# CO2-Ampel_v11.net
KiCad netlist of a schematic drawn in EAGLE
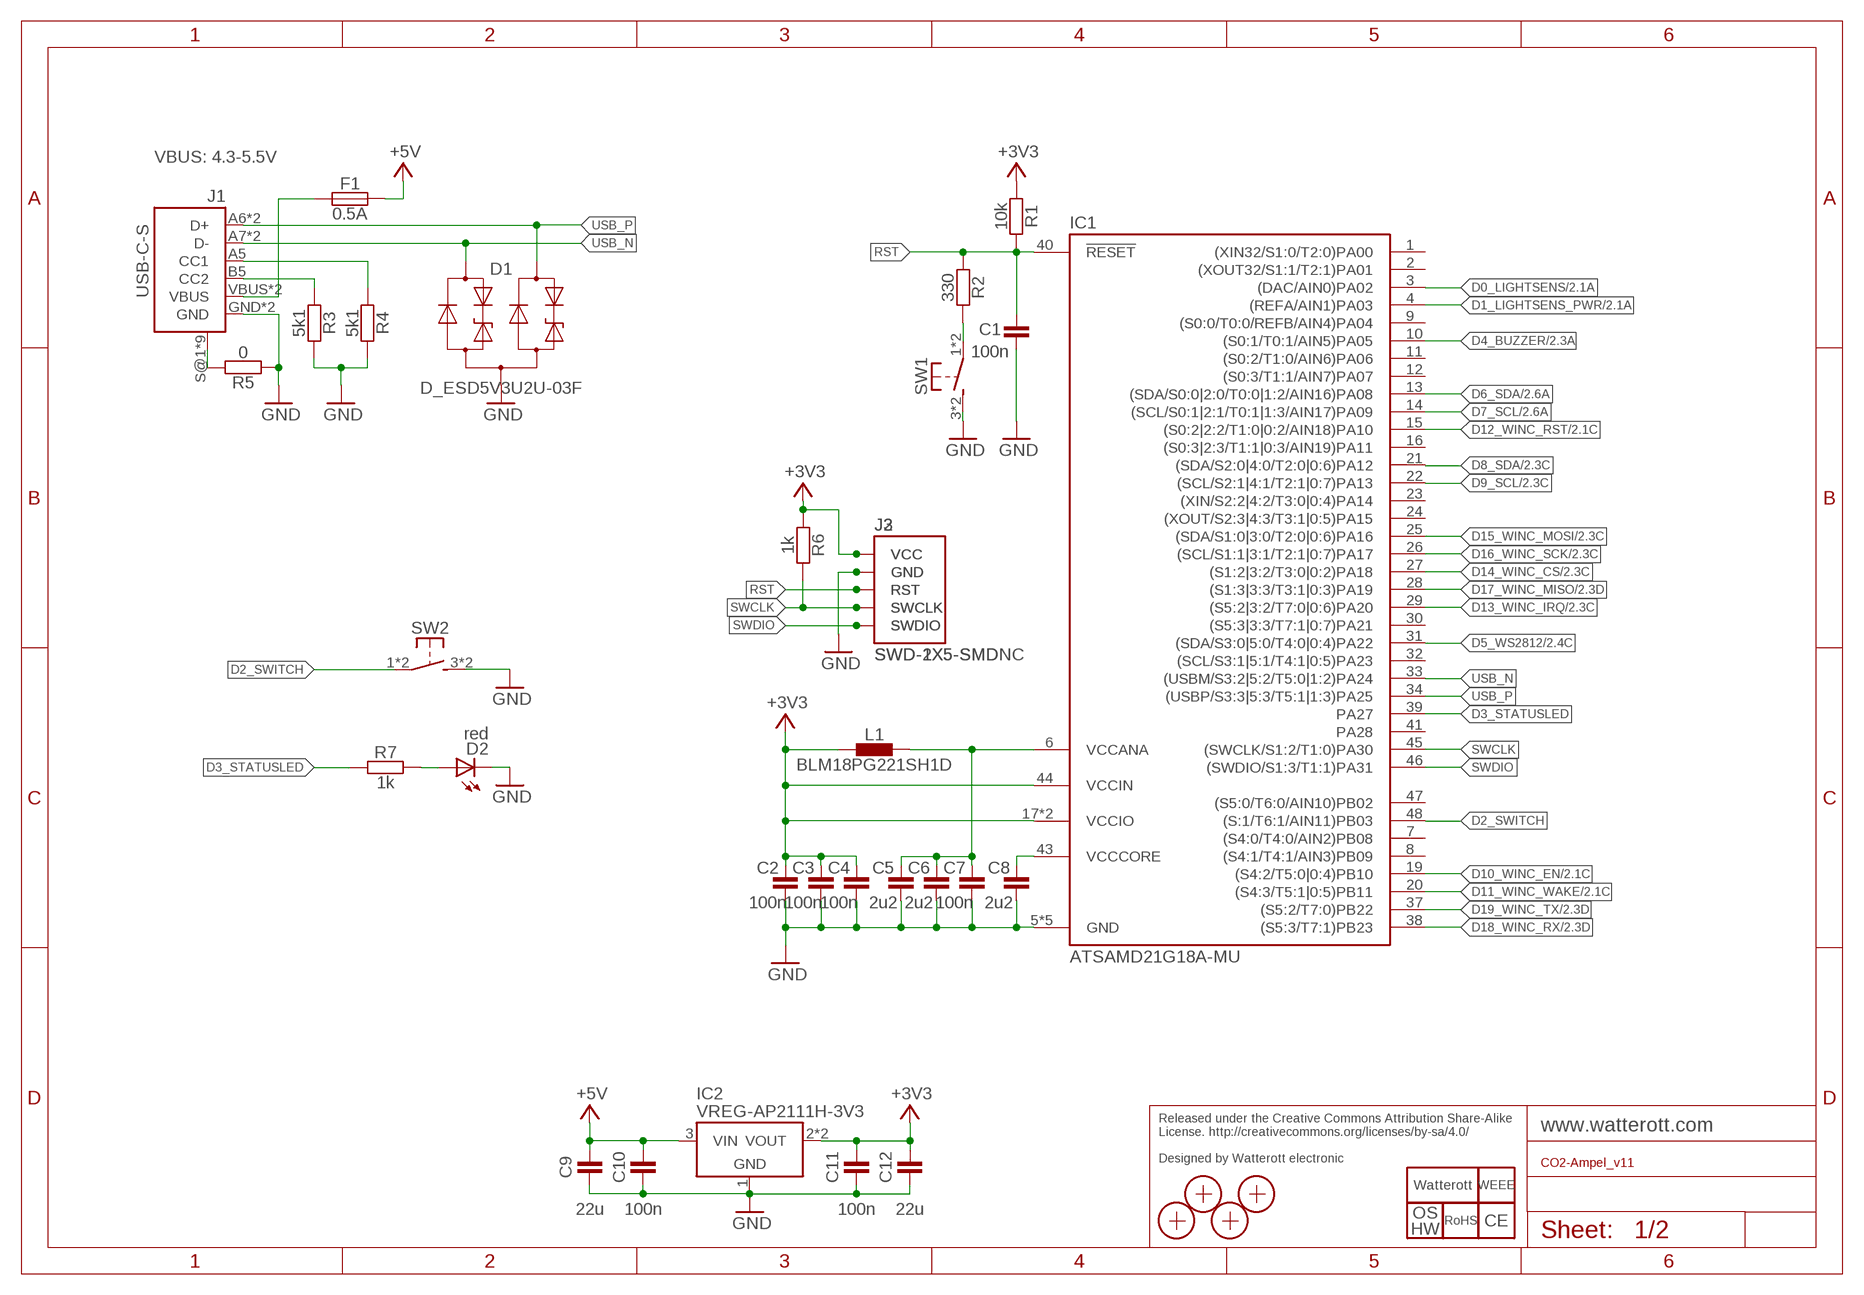
[diagram p0: schematic, sheet 1]
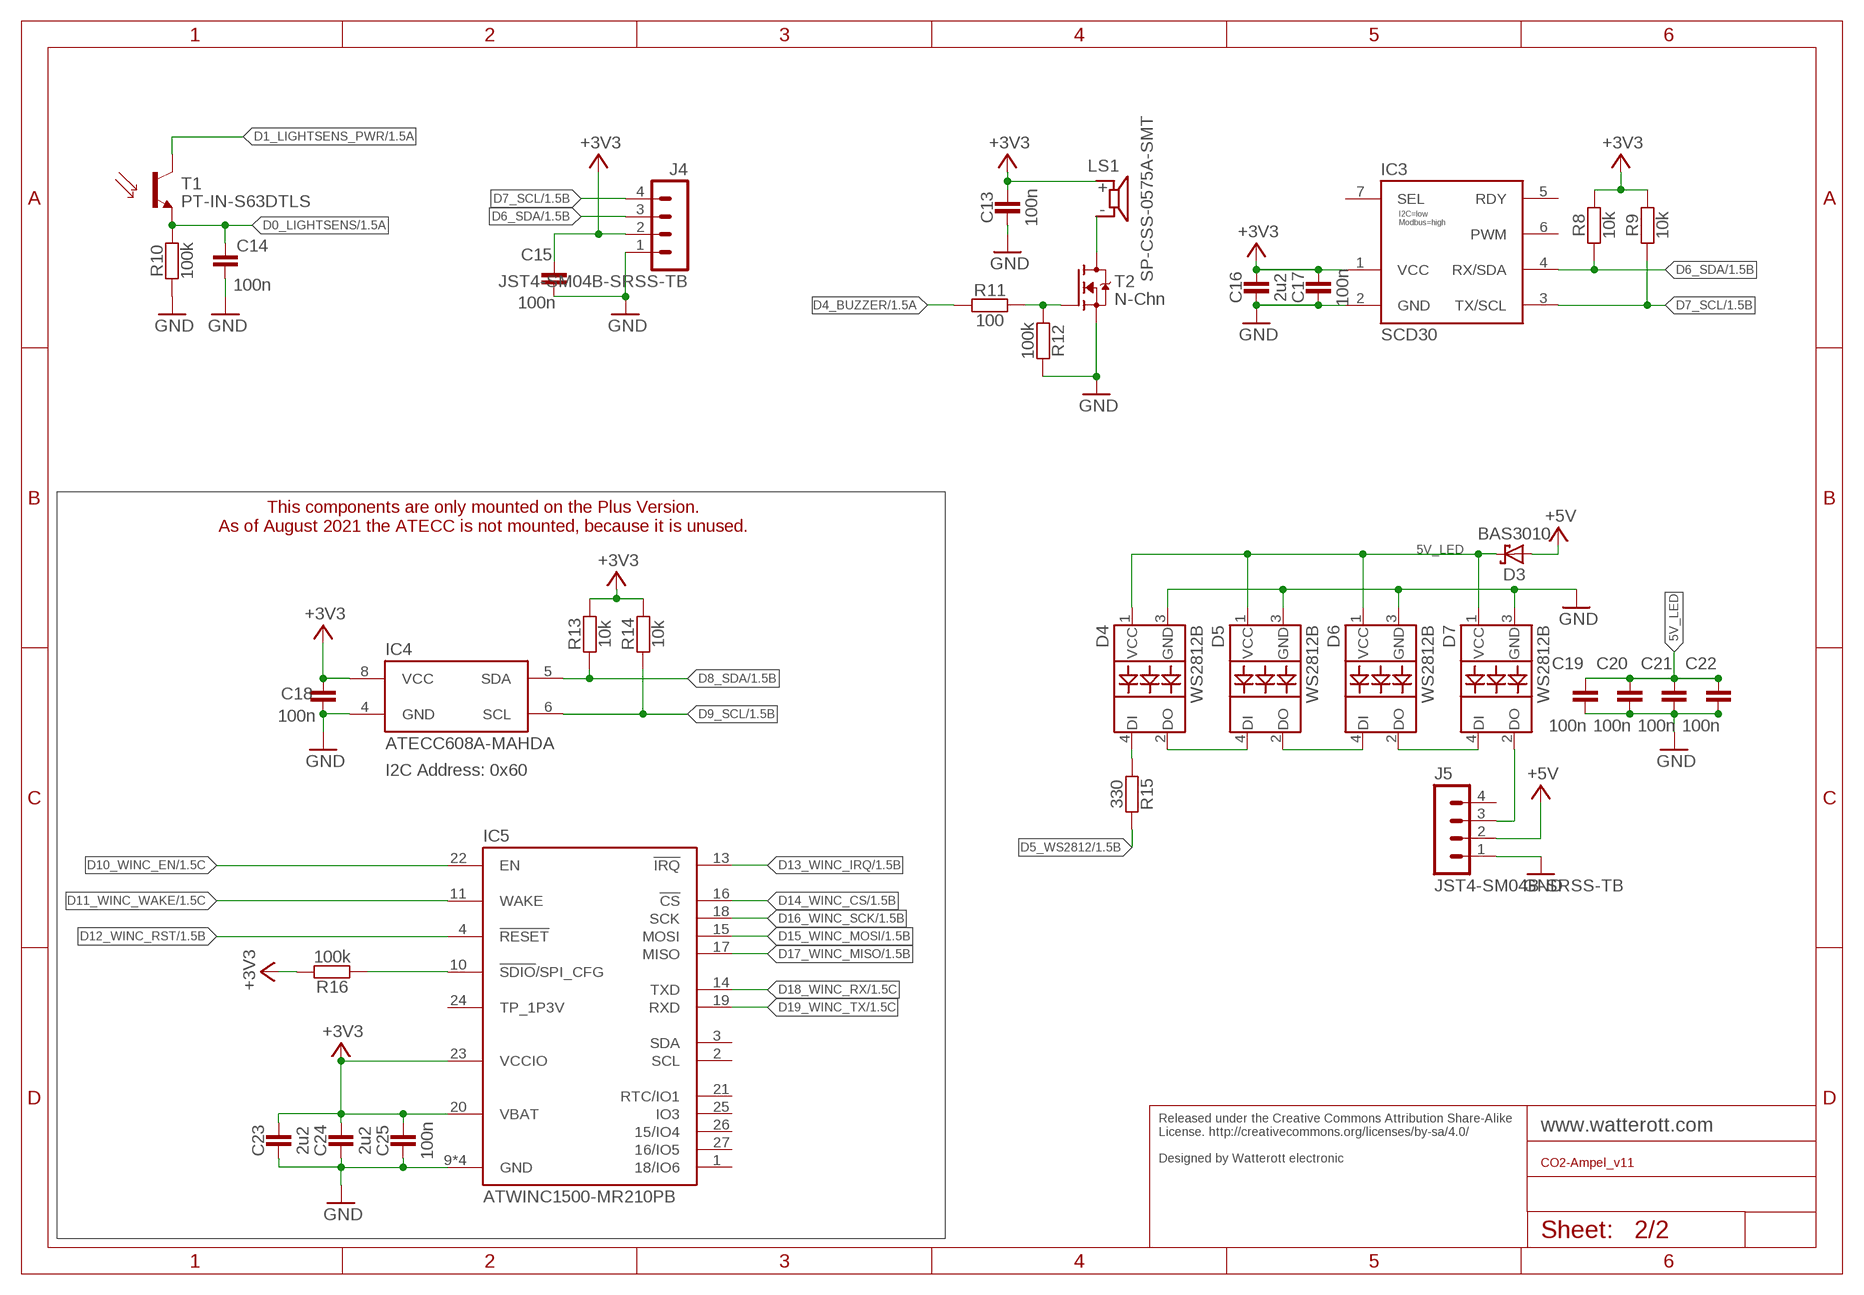
[diagram p1: schematic, sheet 2]

(export (version "E")
  (design (tool "Eeschema 10.0.6"))
  (components
    (comp (ref "C1")
      (value "100n")
      (footprint "eagle-import:C0402")
      (libsource (lib "eagle-import") (part "CAPACITOR-0402"))
    )
    (comp (ref "C2")
      (value "100n")
      (footprint "eagle-import:C0402")
      (libsource (lib "eagle-import") (part "CAPACITOR-0402"))
    )
    (comp (ref "C3")
      (value "100n")
      (footprint "eagle-import:C0402")
      (libsource (lib "eagle-import") (part "CAPACITOR-0402"))
    )
    (comp (ref "C4")
      (value "100n")
      (footprint "eagle-import:C0402")
      (libsource (lib "eagle-import") (part "CAPACITOR-0402"))
    )
    (comp (ref "C5")
      (value "2u2")
      (footprint "eagle-import:C0402")
      (libsource (lib "eagle-import") (part "CAPACITOR-0402"))
    )
    (comp (ref "C6")
      (value "2u2")
      (footprint "eagle-import:C0402")
      (libsource (lib "eagle-import") (part "CAPACITOR-0402"))
    )
    (comp (ref "C7")
      (value "100n")
      (footprint "eagle-import:C0402")
      (libsource (lib "eagle-import") (part "CAPACITOR-0402"))
    )
    (comp (ref "C8")
      (value "2u2")
      (footprint "eagle-import:C0402")
      (libsource (lib "eagle-import") (part "CAPACITOR-0402"))
    )
    (comp (ref "C9")
      (value "22u")
      (footprint "eagle-import:C0805")
      (libsource (lib "eagle-import") (part "CAPACITOR-0805"))
    )
    (comp (ref "C10")
      (value "100n")
      (footprint "eagle-import:C0402")
      (libsource (lib "eagle-import") (part "CAPACITOR-0402"))
    )
    (comp (ref "C11")
      (value "100n")
      (footprint "eagle-import:C0402")
      (libsource (lib "eagle-import") (part "CAPACITOR-0402"))
    )
    (comp (ref "C12")
      (value "22u")
      (footprint "eagle-import:C0805")
      (libsource (lib "eagle-import") (part "CAPACITOR-0805"))
    )
    (comp (ref "D1")
      (value "D_ESD5V3U2U-03F")
      (footprint "eagle-import:SOT723")
      (libsource (lib "eagle-import") (part "D_ESD5V3U2U-03F"))
    )
    (comp (ref "D2")
      (value "red")
      (footprint "eagle-import:C0603")
      (libsource (lib "eagle-import") (part "LED-0603"))
    )
    (comp (ref "F1")
      (value "0.5A")
      (footprint "eagle-import:C0805")
      (libsource (lib "eagle-import") (part "FUSE-0805"))
    )
    (comp (ref "IC1")
      (value "ATSAMD21G18A-MU")
      (footprint "eagle-import:QFN48-PAD")
      (libsource (lib "eagle-import") (part "ATSAMD21G18A-MU"))
    )
    (comp (ref "IC2")
      (value "VREG-AP2111H-3V3")
      (footprint "eagle-import:SOT223")
      (libsource (lib "eagle-import") (part "VREG-TS1117CW-3V3"))
    )
    (comp (ref "J1")
      (value "USB-C-S")
      (footprint "eagle-import:USB-C-S")
      (libsource (lib "eagle-import") (part "USB-C-S"))
    )
    (comp (ref "J2")
      (value "SWD-2X5-SMD")
      (footprint "eagle-import:SWD-2X5_SMD")
      (libsource (lib "eagle-import") (part "SWD-2X5-SMD"))
    )
    (comp (ref "J3")
      (value "SWD-1X5-SMDNC")
      (footprint "eagle-import:SWD-1X5_SMDNC")
      (libsource (lib "eagle-import") (part "SWD-1X5-SMDNC"))
    )
    (comp (ref "L1")
      (value "BLM18PG221SH1D")
      (footprint "eagle-import:C0603")
      (libsource (lib "eagle-import") (part "INDUCTOR-0603"))
    )
    (comp (ref "LOGO1")
      (value "LOGO_SPARK-4")
      (footprint "eagle-import:SPARK_4MM")
      (libsource (lib "eagle-import") (part "LOGO_SPARK-4"))
    )
    (comp (ref "LOGO2")
      (value "LOGO_WEEE-4")
      (footprint "eagle-import:WEEE_4MM")
      (libsource (lib "eagle-import") (part "LOGO_WEEE-4"))
    )
    (comp (ref "LOGO3")
      (value "OSHW_LOGOX0070")
      (footprint "eagle-import:OSHW_3MM")
      (libsource (lib "eagle-import") (part "LOGO_OSHW-3"))
    )
    (comp (ref "LOGO4")
      (value "LOGO_ROHS-4")
      (footprint "eagle-import:ROHS_4MM")
      (libsource (lib "eagle-import") (part "LOGO_ROHS-4"))
    )
    (comp (ref "LOGO5")
      (value "LOGO_CE-4")
      (footprint "eagle-import:CE_4MM")
      (libsource (lib "eagle-import") (part "LOGO_CE-4"))
    )
    (comp (ref "R1")
      (value "10k")
      (footprint "eagle-import:C0402")
      (libsource (lib "eagle-import") (part "RESISTOR-0402"))
    )
    (comp (ref "R2")
      (value "330")
      (footprint "eagle-import:C0402")
      (libsource (lib "eagle-import") (part "RESISTOR-0402"))
    )
    (comp (ref "R3")
      (value "5k1")
      (footprint "eagle-import:C0402")
      (libsource (lib "eagle-import") (part "RESISTOR-0402"))
    )
    (comp (ref "R4")
      (value "5k1")
      (footprint "eagle-import:C0402")
      (libsource (lib "eagle-import") (part "RESISTOR-0402"))
    )
    (comp (ref "R5")
      (value "0")
      (footprint "eagle-import:C0603")
      (libsource (lib "eagle-import") (part "RESISTOR-0603"))
    )
    (comp (ref "R6")
      (value "1k")
      (footprint "eagle-import:C0402")
      (libsource (lib "eagle-import") (part "RESISTOR-0402"))
    )
    (comp (ref "R7")
      (value "1k")
      (footprint "eagle-import:C0402")
      (libsource (lib "eagle-import") (part "RESISTOR-0402"))
    )
    (comp (ref "SW1")
      (value "PTS645SK50SMTR92-Red")
      (footprint "eagle-import:PTS840P")
      (libsource (lib "eagle-import") (part "SW-TACTILE-PTS840P"))
    )
    (comp (ref "SW2")
      (value "PTS645SH50SMTR92-Grey")
      (footprint "eagle-import:PTS840P")
      (libsource (lib "eagle-import") (part "SW-TACTILE-PTS840P"))
    )
    (comp (ref "X1")
      (value "PASSER-07")
      (footprint "eagle-import:PASSER_07MM")
      (libsource (lib "eagle-import") (part "PASSER-07"))
    )
    (comp (ref "X2")
      (value "PASSER-07")
      (footprint "eagle-import:PASSER_07MM")
      (libsource (lib "eagle-import") (part "PASSER-07"))
    )
    (comp (ref "X3")
      (value "PASSER-07")
      (footprint "eagle-import:PASSER_07MM")
      (libsource (lib "eagle-import") (part "PASSER-07"))
    )
    (comp (ref "X4")
      (value "PASSER-07")
      (footprint "eagle-import:PASSER_07MM")
      (libsource (lib "eagle-import") (part "PASSER-07"))
    )
    (comp (ref "C13")
      (value "100n")
      (footprint "eagle-import:C0402")
      (libsource (lib "eagle-import") (part "CAPACITOR-0402"))
    )
    (comp (ref "C14")
      (value "100n")
      (footprint "eagle-import:C0402")
      (libsource (lib "eagle-import") (part "CAPACITOR-0402"))
    )
    (comp (ref "C15")
      (value "100n")
      (footprint "eagle-import:C0402")
      (libsource (lib "eagle-import") (part "CAPACITOR-0402"))
    )
    (comp (ref "C16")
      (value "2u2")
      (footprint "eagle-import:C0402")
      (libsource (lib "eagle-import") (part "CAPACITOR-0402"))
    )
    (comp (ref "C17")
      (value "100n")
      (footprint "eagle-import:C0402")
      (libsource (lib "eagle-import") (part "CAPACITOR-0402"))
    )
    (comp (ref "C18")
      (value "100n")
      (footprint "eagle-import:C0402")
      (libsource (lib "eagle-import") (part "CAPACITOR-0402"))
    )
    (comp (ref "C19")
      (value "100n")
      (footprint "eagle-import:C0402")
      (libsource (lib "eagle-import") (part "CAPACITOR-0402"))
    )
    (comp (ref "C20")
      (value "100n")
      (footprint "eagle-import:C0402")
      (libsource (lib "eagle-import") (part "CAPACITOR-0402"))
    )
    (comp (ref "C21")
      (value "100n")
      (footprint "eagle-import:C0402")
      (libsource (lib "eagle-import") (part "CAPACITOR-0402"))
    )
    (comp (ref "C22")
      (value "100n")
      (footprint "eagle-import:C0402")
      (libsource (lib "eagle-import") (part "CAPACITOR-0402"))
    )
    (comp (ref "C23")
      (value "2u2")
      (footprint "eagle-import:C0402")
      (libsource (lib "eagle-import") (part "CAPACITOR-0402"))
    )
    (comp (ref "C24")
      (value "2u2")
      (footprint "eagle-import:C0402")
      (libsource (lib "eagle-import") (part "CAPACITOR-0402"))
    )
    (comp (ref "C25")
      (value "100n")
      (footprint "eagle-import:C0402")
      (libsource (lib "eagle-import") (part "CAPACITOR-0402"))
    )
    (comp (ref "D3")
      (value "BAS3010")
      (footprint "eagle-import:SOD323")
      (libsource (lib "eagle-import") (part "D_SCHOTTKY-SOD323"))
    )
    (comp (ref "D4")
      (value "WS2812B")
      (footprint "eagle-import:WS2812B")
      (libsource (lib "eagle-import") (part "WS2812B"))
    )
    (comp (ref "D5")
      (value "WS2812B")
      (footprint "eagle-import:WS2812B")
      (libsource (lib "eagle-import") (part "WS2812B"))
    )
    (comp (ref "D6")
      (value "WS2812B")
      (footprint "eagle-import:WS2812B")
      (libsource (lib "eagle-import") (part "WS2812B"))
    )
    (comp (ref "D7")
      (value "WS2812B")
      (footprint "eagle-import:WS2812B")
      (libsource (lib "eagle-import") (part "WS2812B"))
    )
    (comp (ref "IC3")
      (value "SCD30")
      (footprint "eagle-import:SCD30")
      (libsource (lib "eagle-import") (part "SCD30"))
    )
    (comp (ref "IC4")
      (value "ATECC608A-MAHDA")
      (footprint "eagle-import:UDFN8")
      (libsource (lib "eagle-import") (part "ATECC608A-MAHDA"))
    )
    (comp (ref "IC5")
      (value "ATWINC1500-MR210PB")
      (footprint "eagle-import:ATWINC1500-MX210")
      (libsource (lib "eagle-import") (part "ATWINC1500-MR210PB"))
    )
    (comp (ref "J4")
      (value "JST4-SM04B-SRSS-TB")
      (footprint "eagle-import:JST_SM04B-SRSS-TB")
      (libsource (lib "eagle-import") (part "JST4-SM04B-SRSS-TB"))
    )
    (comp (ref "J5")
      (value "JST4-SM04B-SRSS-TB")
      (footprint "eagle-import:JST_SM04B-SRSS-TB")
      (libsource (lib "eagle-import") (part "JST4-SM04B-SRSS-TB"))
    )
    (comp (ref "LS1")
      (value "SP-CSS-0575A-SMT")
      (footprint "eagle-import:CUI_CSS-0575A-SMT")
      (fields (field (name "MF") "CUI") (field (name "MPN") "CSS-0575A-SMT"))
      (libsource (lib "eagle-import") (part "SP-CSS-0575A-SMT"))
    )
    (comp (ref "R8")
      (value "10k")
      (footprint "eagle-import:C0402")
      (libsource (lib "eagle-import") (part "RESISTOR-0402"))
    )
    (comp (ref "R9")
      (value "10k")
      (footprint "eagle-import:C0402")
      (libsource (lib "eagle-import") (part "RESISTOR-0402"))
    )
    (comp (ref "R10")
      (value "100k")
      (footprint "eagle-import:C0402")
      (libsource (lib "eagle-import") (part "RESISTOR-0402"))
    )
    (comp (ref "R11")
      (value "100")
      (footprint "eagle-import:C0402")
      (libsource (lib "eagle-import") (part "RESISTOR-0402"))
    )
    (comp (ref "R12")
      (value "100k")
      (footprint "eagle-import:C0402")
      (libsource (lib "eagle-import") (part "RESISTOR-0402"))
    )
    (comp (ref "R13")
      (value "10k")
      (footprint "eagle-import:C0402")
      (libsource (lib "eagle-import") (part "RESISTOR-0402"))
    )
    (comp (ref "R14")
      (value "10k")
      (footprint "eagle-import:C0402")
      (libsource (lib "eagle-import") (part "RESISTOR-0402"))
    )
    (comp (ref "R15")
      (value "330")
      (footprint "eagle-import:C0402")
      (libsource (lib "eagle-import") (part "RESISTOR-0402"))
    )
    (comp (ref "R16")
      (value "100k")
      (footprint "eagle-import:C0402")
      (libsource (lib "eagle-import") (part "RESISTOR-0402"))
    )
    (comp (ref "T1")
      (value "PT-IN-S63DTLS")
      (footprint "eagle-import:C0603T")
      (libsource (lib "eagle-import") (part "PT-IN-S63DTLS"))
    )
    (comp (ref "T2")
      (value "N-Chn")
      (footprint "eagle-import:SOT23")
      (libsource (lib "eagle-import") (part "MOSFET-N-SOT23"))
    )
  )
  (nets
    (net (code "1") (name "+3V3") (class "Default")
      (node (ref "C11") (pin "2") (pinfunction "2_2") (pintype "passive"))
      (node (ref "C12") (pin "2") (pinfunction "2_2") (pintype "passive"))
      (node (ref "C13") (pin "2") (pinfunction "2_2") (pintype "passive"))
      (node (ref "C15") (pin "2") (pinfunction "2_2") (pintype "passive"))
      (node (ref "C16") (pin "2") (pinfunction "2_2") (pintype "passive"))
      (node (ref "C17") (pin "2") (pinfunction "2_2") (pintype "passive"))
      (node (ref "C18") (pin "2") (pinfunction "2_2") (pintype "passive"))
      (node (ref "C2") (pin "2") (pinfunction "2_2") (pintype "passive"))
      (node (ref "C23") (pin "2") (pinfunction "2_2") (pintype "passive"))
      (node (ref "C24") (pin "2") (pinfunction "2_2") (pintype "passive"))
      (node (ref "C25") (pin "2") (pinfunction "2_2") (pintype "passive"))
      (node (ref "C3") (pin "2") (pinfunction "2_2") (pintype "passive"))
      (node (ref "C4") (pin "2") (pinfunction "2_2") (pintype "passive"))
      (node (ref "IC1") (pin "17") (pinfunction "VCCIO_17") (pintype "power_in"))
      (node (ref "IC1") (pin "36") (pinfunction "VCCIO_36") (pintype "power_in"))
      (node (ref "IC1") (pin "44") (pinfunction "VCCIN_44") (pintype "power_in"))
      (node (ref "IC2") (pin "2") (pinfunction "VOUT_2") (pintype "power_in"))
      (node (ref "IC2") (pin "4") (pinfunction "VOUT_4") (pintype "power_in"))
      (node (ref "IC3") (pin "1") (pinfunction "VCC_1") (pintype "power_in"))
      (node (ref "IC4") (pin "8") (pinfunction "VCC_8") (pintype "power_in"))
      (node (ref "IC5") (pin "20") (pinfunction "VBAT_20") (pintype "power_in"))
      (node (ref "IC5") (pin "23") (pinfunction "VCCIO_23") (pintype "power_in"))
      (node (ref "J2") (pin "VCC") (pinfunction "VCC_VCC") (pintype "power_in"))
      (node (ref "J3") (pin "1-VCC") (pinfunction "VCC_1-VCC") (pintype "power_in"))
      (node (ref "J4") (pin "2") (pinfunction "2_2") (pintype "passive"))
      (node (ref "L1") (pin "1") (pinfunction "1_1") (pintype "passive"))
      (node (ref "LS1") (pin "+") (pinfunction "P_+") (pintype "passive"))
      (node (ref "R1") (pin "1") (pinfunction "1_1") (pintype "passive"))
      (node (ref "R13") (pin "2") (pinfunction "2_2") (pintype "passive"))
      (node (ref "R14") (pin "2") (pinfunction "2_2") (pintype "passive"))
      (node (ref "R16") (pin "2") (pinfunction "2_2") (pintype "passive"))
      (node (ref "R6") (pin "1") (pinfunction "1_1") (pintype "passive"))
      (node (ref "R8") (pin "2") (pinfunction "2_2") (pintype "passive"))
      (node (ref "R9") (pin "2") (pinfunction "2_2") (pintype "passive"))
    )
    (net (code "2") (name "+5V") (class "Default")
      (node (ref "C10") (pin "2") (pinfunction "2_2") (pintype "passive"))
      (node (ref "C9") (pin "2") (pinfunction "2_2") (pintype "passive"))
      (node (ref "D3") (pin "A") (pinfunction "A_A") (pintype "passive"))
      (node (ref "F1") (pin "2") (pinfunction "2_2") (pintype "passive"))
      (node (ref "IC2") (pin "3") (pinfunction "VIN_3") (pintype "power_in"))
      (node (ref "J5") (pin "2") (pinfunction "2_2") (pintype "passive"))
    )
    (net (code "3") (name "5V_LED") (class "Default")
      (node (ref "C19") (pin "2") (pinfunction "2_2") (pintype "passive"))
      (node (ref "C20") (pin "2") (pinfunction "2_2") (pintype "passive"))
      (node (ref "C21") (pin "2") (pinfunction "2_2") (pintype "passive"))
      (node (ref "C22") (pin "2") (pinfunction "2_2") (pintype "passive"))
      (node (ref "D3") (pin "C") (pinfunction "C_C") (pintype "passive"))
      (node (ref "D4") (pin "1") (pinfunction "VCC_1") (pintype "power_in"))
      (node (ref "D5") (pin "1") (pinfunction "VCC_1") (pintype "power_in"))
      (node (ref "D6") (pin "1") (pinfunction "VCC_1") (pintype "power_in"))
      (node (ref "D7") (pin "1") (pinfunction "VCC_1") (pintype "power_in"))
    )
    (net (code "4") (name "D0_LIGHTSENS") (class "Default")
      (node (ref "C14") (pin "2") (pinfunction "2_2") (pintype "passive"))
      (node (ref "IC1") (pin "3") (pinfunction "(DAC/AIN0)PA02_3") (pintype "bidirectional"))
      (node (ref "R10") (pin "2") (pinfunction "2_2") (pintype "passive"))
      (node (ref "T1") (pin "E") (pinfunction "E_E") (pintype "passive"))
    )
    (net (code "5") (name "D1_LIGHTSENS_PWR") (class "Default")
      (node (ref "IC1") (pin "4") (pinfunction "(REFA/AIN1)PA03_4") (pintype "bidirectional"))
      (node (ref "T1") (pin "C") (pinfunction "C_C") (pintype "passive"))
    )
    (net (code "6") (name "D2_SWITCH") (class "Default")
      (node (ref "IC1") (pin "48") (pinfunction "(S:1/T6:1/AIN11)PB03_48") (pintype "bidirectional"))
      (node (ref "SW2") (pin "1") (pinfunction "P1_1") (pintype "passive"))
      (node (ref "SW2") (pin "2") (pinfunction "P1_2") (pintype "passive"))
    )
    (net (code "7") (name "D3_STATUSLED") (class "Default")
      (node (ref "IC1") (pin "39") (pinfunction "PA27_39") (pintype "bidirectional"))
      (node (ref "R7") (pin "1") (pinfunction "1_1") (pintype "passive"))
    )
    (net (code "8") (name "D4_BUZZER") (class "Default")
      (node (ref "IC1") (pin "10") (pinfunction "(S0:1/T0:1/AIN5)PA05_10") (pintype "bidirectional"))
      (node (ref "R11") (pin "1") (pinfunction "1_1") (pintype "passive"))
    )
    (net (code "9") (name "D5_WS2812") (class "Default")
      (node (ref "IC1") (pin "31") (pinfunction "(SDA/S3:0|5:0/T4:0|0:4)PA22_31") (pintype "bidirectional"))
      (node (ref "R15") (pin "2") (pinfunction "2_2") (pintype "passive"))
    )
    (net (code "10") (name "D6_SDA") (class "Default")
      (node (ref "IC1") (pin "13") (pinfunction "(SDA/S0:0|2:0/T0:0|1:2/AIN16)PA08_13") (pintype "bidirectional"))
      (node (ref "IC3") (pin "4") (pinfunction "RX/SDA_4") (pintype "bidirectional"))
      (node (ref "J4") (pin "3") (pinfunction "3_3") (pintype "passive"))
      (node (ref "R8") (pin "1") (pinfunction "1_1") (pintype "passive"))
    )
    (net (code "11") (name "D7_SCL") (class "Default")
      (node (ref "IC1") (pin "14") (pinfunction "(SCL/S0:1|2:1/T0:1|1:3/AIN17)PA09_14") (pintype "bidirectional"))
      (node (ref "IC3") (pin "3") (pinfunction "TX/SCL_3") (pintype "bidirectional"))
      (node (ref "J4") (pin "4") (pinfunction "4_4") (pintype "passive"))
      (node (ref "R9") (pin "1") (pinfunction "1_1") (pintype "passive"))
    )
    (net (code "12") (name "D8_SDA") (class "Default")
      (node (ref "IC1") (pin "21") (pinfunction "(SDA/S2:0|4:0/T2:0|0:6)PA12_21") (pintype "bidirectional"))
      (node (ref "IC4") (pin "5") (pinfunction "SDA_5") (pintype "bidirectional"))
      (node (ref "R13") (pin "1") (pinfunction "1_1") (pintype "passive"))
    )
    (net (code "13") (name "D9_SCL") (class "Default")
      (node (ref "IC1") (pin "22") (pinfunction "(SCL/S2:1|4:1/T2:1|0:7)PA13_22") (pintype "bidirectional"))
      (node (ref "IC4") (pin "6") (pinfunction "SCL_6") (pintype "bidirectional"))
      (node (ref "R14") (pin "1") (pinfunction "1_1") (pintype "passive"))
    )
    (net (code "14") (name "D10_WINC_EN") (class "Default")
      (node (ref "IC1") (pin "19") (pinfunction "(S4:2/T5:0|0:4)PB10_19") (pintype "bidirectional"))
      (node (ref "IC5") (pin "22") (pinfunction "EN_22") (pintype "input"))
    )
    (net (code "15") (name "D11_WINC_WAKE") (class "Default")
      (node (ref "IC1") (pin "20") (pinfunction "(S4:3/T5:1|0:5)PB11_20") (pintype "bidirectional"))
      (node (ref "IC5") (pin "11") (pinfunction "WAKE_11") (pintype "input"))
    )
    (net (code "16") (name "D12_WINC_RST") (class "Default")
      (node (ref "IC1") (pin "15") (pinfunction "(S0:2|2:2/T1:0|0:2/AIN18)PA10_15") (pintype "bidirectional"))
      (node (ref "IC5") (pin "4") (pinfunction "~{RESET}_4") (pintype "input"))
    )
    (net (code "17") (name "D13_WINC_IRQ") (class "Default")
      (node (ref "IC1") (pin "29") (pinfunction "(S5:2|3:2/T7:0|0:6)PA20_29") (pintype "bidirectional"))
      (node (ref "IC5") (pin "13") (pinfunction "~{IRQ}_13") (pintype "output"))
    )
    (net (code "18") (name "D14_WINC_CS") (class "Default")
      (node (ref "IC1") (pin "27") (pinfunction "(S1:2|3:2/T3:0|0:2)PA18_27") (pintype "bidirectional"))
      (node (ref "IC5") (pin "16") (pinfunction "~{CS}_16") (pintype "input"))
    )
    (net (code "19") (name "D15_WINC_MOSI") (class "Default")
      (node (ref "IC1") (pin "25") (pinfunction "(SDA/S1:0|3:0/T2:0|0:6)PA16_25") (pintype "bidirectional"))
      (node (ref "IC5") (pin "15") (pinfunction "MOSI_15") (pintype "input"))
    )
    (net (code "20") (name "D16_WINC_SCK") (class "Default")
      (node (ref "IC1") (pin "26") (pinfunction "(SCL/S1:1|3:1/T2:1|0:7)PA17_26") (pintype "bidirectional"))
      (node (ref "IC5") (pin "18") (pinfunction "SCK_18") (pintype "input"))
    )
    (net (code "21") (name "D17_WINC_MISO") (class "Default")
      (node (ref "IC1") (pin "28") (pinfunction "(S1:3|3:3/T3:1|0:3)PA19_28") (pintype "bidirectional"))
      (node (ref "IC5") (pin "17") (pinfunction "MISO_17") (pintype "output"))
    )
    (net (code "22") (name "D18_WINC_RX") (class "Default")
      (node (ref "IC1") (pin "38") (pinfunction "(S5:3/T7:1)PB23_38") (pintype "bidirectional"))
      (node (ref "IC5") (pin "14") (pinfunction "TXD_14") (pintype "output"))
    )
    (net (code "23") (name "D19_WINC_TX") (class "Default")
      (node (ref "IC1") (pin "37") (pinfunction "(S5:2/T7:0)PB22_37") (pintype "bidirectional"))
      (node (ref "IC5") (pin "19") (pinfunction "RXD_19") (pintype "input"))
    )
    (net (code "24") (name "GND") (class "Default")
      (node (ref "C1") (pin "1") (pinfunction "1_1") (pintype "passive"))
      (node (ref "C10") (pin "1") (pinfunction "1_1") (pintype "passive"))
      (node (ref "C11") (pin "1") (pinfunction "1_1") (pintype "passive"))
      (node (ref "C12") (pin "1") (pinfunction "1_1") (pintype "passive"))
      (node (ref "C13") (pin "1") (pinfunction "1_1") (pintype "passive"))
      (node (ref "C14") (pin "1") (pinfunction "1_1") (pintype "passive"))
      (node (ref "C15") (pin "1") (pinfunction "1_1") (pintype "passive"))
      (node (ref "C16") (pin "1") (pinfunction "1_1") (pintype "passive"))
      (node (ref "C17") (pin "1") (pinfunction "1_1") (pintype "passive"))
      (node (ref "C18") (pin "1") (pinfunction "1_1") (pintype "passive"))
      (node (ref "C19") (pin "1") (pinfunction "1_1") (pintype "passive"))
      (node (ref "C2") (pin "1") (pinfunction "1_1") (pintype "passive"))
      (node (ref "C20") (pin "1") (pinfunction "1_1") (pintype "passive"))
      (node (ref "C21") (pin "1") (pinfunction "1_1") (pintype "passive"))
      (node (ref "C22") (pin "1") (pinfunction "1_1") (pintype "passive"))
      (node (ref "C23") (pin "1") (pinfunction "1_1") (pintype "passive"))
      (node (ref "C24") (pin "1") (pinfunction "1_1") (pintype "passive"))
      (node (ref "C25") (pin "1") (pinfunction "1_1") (pintype "passive"))
      (node (ref "C3") (pin "1") (pinfunction "1_1") (pintype "passive"))
      (node (ref "C4") (pin "1") (pinfunction "1_1") (pintype "passive"))
      (node (ref "C5") (pin "1") (pinfunction "1_1") (pintype "passive"))
      (node (ref "C6") (pin "1") (pinfunction "1_1") (pintype "passive"))
      (node (ref "C7") (pin "1") (pinfunction "1_1") (pintype "passive"))
      (node (ref "C8") (pin "1") (pinfunction "1_1") (pintype "passive"))
      (node (ref "C9") (pin "1") (pinfunction "1_1") (pintype "passive"))
      (node (ref "D1") (pin "3") (pinfunction "A_3") (pintype "passive"))
      (node (ref "D2") (pin "C") (pinfunction "C_C") (pintype "passive"))
      (node (ref "D4") (pin "3") (pinfunction "GND_3") (pintype "power_in"))
      (node (ref "D5") (pin "3") (pinfunction "GND_3") (pintype "power_in"))
      (node (ref "D6") (pin "3") (pinfunction "GND_3") (pintype "power_in"))
      (node (ref "D7") (pin "3") (pinfunction "GND_3") (pintype "power_in"))
      (node (ref "IC1") (pin "18") (pinfunction "GND_18") (pintype "power_in"))
      (node (ref "IC1") (pin "35") (pinfunction "GND_35") (pintype "power_in"))
      (node (ref "IC1") (pin "42") (pinfunction "GND_42") (pintype "power_in"))
      (node (ref "IC1") (pin "5") (pinfunction "GND_5") (pintype "power_in"))
      (node (ref "IC1") (pin "TP") (pinfunction "GND_TP") (pintype "power_in"))
      (node (ref "IC2") (pin "1") (pinfunction "GND_1") (pintype "power_in"))
      (node (ref "IC3") (pin "2") (pinfunction "GND_2") (pintype "power_in"))
      (node (ref "IC4") (pin "4") (pinfunction "GND_4") (pintype "power_in"))
      (node (ref "IC5") (pin "12") (pinfunction "GND_12") (pintype "power_in"))
      (node (ref "IC5") (pin "28") (pinfunction "GND_28") (pintype "power_in"))
      (node (ref "IC5") (pin "9") (pinfunction "GND_9") (pintype "power_in"))
      (node (ref "IC5") (pin "GND") (pinfunction "GND_GND") (pintype "power_in"))
      (node (ref "J1") (pin "GND") (pinfunction "GND_GND") (pintype "power_in"))
      (node (ref "J1") (pin "GND2") (pinfunction "GND_GND2") (pintype "power_in"))
      (node (ref "J2") (pin "GND@1") (pinfunction "GND_GND@1") (pintype "power_in"))
      (node (ref "J2") (pin "GND@2") (pinfunction "GND_GND@2") (pintype "power_in"))
      (node (ref "J2") (pin "GND@3") (pinfunction "GND_GND@3") (pintype "power_in"))
      (node (ref "J3") (pin "2-GND") (pinfunction "GND_2-GND") (pintype "power_in"))
      (node (ref "J4") (pin "1") (pinfunction "1_1") (pintype "passive"))
      (node (ref "J5") (pin "1") (pinfunction "1_1") (pintype "passive"))
      (node (ref "R10") (pin "1") (pinfunction "1_1") (pintype "passive"))
      (node (ref "R12") (pin "2") (pinfunction "2_2") (pintype "passive"))
      (node (ref "R3") (pin "2") (pinfunction "2_2") (pintype "passive"))
      (node (ref "R4") (pin "2") (pinfunction "2_2") (pintype "passive"))
      (node (ref "R5") (pin "1") (pinfunction "1_1") (pintype "passive"))
      (node (ref "SW1") (pin "3") (pinfunction "S1_3") (pintype "passive"))
      (node (ref "SW1") (pin "4") (pinfunction "S1_4") (pintype "passive"))
      (node (ref "SW2") (pin "3") (pinfunction "S1_3") (pintype "passive"))
      (node (ref "SW2") (pin "4") (pinfunction "S1_4") (pintype "passive"))
      (node (ref "T2") (pin "2") (pinfunction "S_2") (pintype "passive"))
    )
    (net (code "25") (name "Net-(D2-PadA)") (class "Default")
      (node (ref "D2") (pin "A") (pinfunction "A_A") (pintype "passive"))
      (node (ref "R7") (pin "2") (pinfunction "2_2") (pintype "passive"))
    )
    (net (code "26") (name "Net-(D4-DI)") (class "Default")
      (node (ref "D4") (pin "4") (pinfunction "DI_4") (pintype "bidirectional"))
      (node (ref "R15") (pin "1") (pinfunction "1_1") (pintype "passive"))
    )
    (net (code "27") (name "Net-(D4-DO)") (class "Default")
      (node (ref "D4") (pin "2") (pinfunction "DO_2") (pintype "bidirectional"))
      (node (ref "D5") (pin "4") (pinfunction "DI_4") (pintype "bidirectional"))
    )
    (net (code "28") (name "Net-(D5-DO)") (class "Default")
      (node (ref "D5") (pin "2") (pinfunction "DO_2") (pintype "bidirectional"))
      (node (ref "D6") (pin "4") (pinfunction "DI_4") (pintype "bidirectional"))
    )
    (net (code "29") (name "Net-(D6-DO)") (class "Default")
      (node (ref "D6") (pin "2") (pinfunction "DO_2") (pintype "bidirectional"))
      (node (ref "D7") (pin "4") (pinfunction "DI_4") (pintype "bidirectional"))
    )
    (net (code "30") (name "Net-(D7-DO)") (class "Default")
      (node (ref "D7") (pin "2") (pinfunction "DO_2") (pintype "bidirectional"))
      (node (ref "J5") (pin "3") (pinfunction "3_3") (pintype "passive"))
    )
    (net (code "31") (name "Net-(F1-Pad1)") (class "Default")
      (node (ref "F1") (pin "1") (pinfunction "1_1") (pintype "passive"))
      (node (ref "J1") (pin "VBUS") (pinfunction "VBUS_VBUS") (pintype "power_in"))
      (node (ref "J1") (pin "VBUS2") (pinfunction "VBUS_VBUS2") (pintype "power_in"))
    )
    (net (code "32") (name "Net-(IC1-VCCANA)") (class "Default")
      (node (ref "C5") (pin "2") (pinfunction "2_2") (pintype "passive"))
      (node (ref "C6") (pin "2") (pinfunction "2_2") (pintype "passive"))
      (node (ref "C7") (pin "2") (pinfunction "2_2") (pintype "passive"))
      (node (ref "IC1") (pin "6") (pinfunction "VCCANA_6") (pintype "power_in"))
      (node (ref "L1") (pin "2") (pinfunction "2_2") (pintype "passive"))
    )
    (net (code "33") (name "Net-(IC1-VCCCORE)") (class "Default")
      (node (ref "C8") (pin "2") (pinfunction "2_2") (pintype "passive"))
      (node (ref "IC1") (pin "43") (pinfunction "VCCCORE_43") (pintype "power_in"))
    )
    (net (code "34") (name "Net-(IC5-~{SDIO}{slash}SPI_CFG)") (class "Default")
      (node (ref "IC5") (pin "10") (pinfunction "~{SDIO}/SPI_CFG_10") (pintype "input"))
      (node (ref "R16") (pin "1") (pinfunction "1_1") (pintype "passive"))
    )
    (net (code "35") (name "Net-(J1-CC1)") (class "Default")
      (node (ref "J1") (pin "A5") (pinfunction "CC1_A5") (pintype "bidirectional"))
      (node (ref "R4") (pin "1") (pinfunction "1_1") (pintype "passive"))
    )
    (net (code "36") (name "Net-(J1-CC2)") (class "Default")
      (node (ref "J1") (pin "B5") (pinfunction "CC2_B5") (pintype "bidirectional"))
      (node (ref "R3") (pin "1") (pinfunction "1_1") (pintype "passive"))
    )
    (net (code "37") (name "Net-(J1-SHIELD-PadS@1)") (class "Default")
      (node (ref "J1") (pin "S@1") (pinfunction "SHIELD_S@1") (pintype "passive"))
      (node (ref "J1") (pin "S@2") (pinfunction "SHIELD_S@2") (pintype "passive"))
      (node (ref "J1") (pin "S@3") (pinfunction "SHIELD_S@3") (pintype "passive"))
      (node (ref "J1") (pin "S@4") (pinfunction "SHIELD_S@4") (pintype "passive"))
      (node (ref "J1") (pin "S@5") (pinfunction "SHIELD_S@5") (pintype "passive"))
      (node (ref "J1") (pin "S@6") (pinfunction "SHIELD_S@6") (pintype "passive"))
      (node (ref "J1") (pin "S@7") (pinfunction "SHIELD_S@7") (pintype "passive"))
      (node (ref "J1") (pin "S@8") (pinfunction "SHIELD_S@8") (pintype "passive"))
      (node (ref "J1") (pin "S@9") (pinfunction "SHIELD_S@9") (pintype "passive"))
      (node (ref "R5") (pin "2") (pinfunction "2_2") (pintype "passive"))
    )
    (net (code "38") (name "Net-(LS1-N)") (class "Default")
      (node (ref "LS1") (pin "-") (pinfunction "N_-") (pintype "passive"))
      (node (ref "T2") (pin "3") (pinfunction "D_3") (pintype "passive"))
    )
    (net (code "39") (name "Net-(R2-Pad2)") (class "Default")
      (node (ref "R2") (pin "2") (pinfunction "2_2") (pintype "passive"))
      (node (ref "SW1") (pin "1") (pinfunction "P1_1") (pintype "passive"))
      (node (ref "SW1") (pin "2") (pinfunction "P1_2") (pintype "passive"))
    )
    (net (code "40") (name "Net-(T2-G)") (class "Default")
      (node (ref "R11") (pin "2") (pinfunction "2_2") (pintype "passive"))
      (node (ref "R12") (pin "1") (pinfunction "1_1") (pintype "passive"))
      (node (ref "T2") (pin "1") (pinfunction "G_1") (pintype "passive"))
    )
    (net (code "41") (name "RST") (class "Default")
      (node (ref "C1") (pin "2") (pinfunction "2_2") (pintype "passive"))
      (node (ref "IC1") (pin "40") (pinfunction "~{RESET}_40") (pintype "input"))
      (node (ref "J2") (pin "RST") (pinfunction "RST_RST") (pintype "bidirectional"))
      (node (ref "J3") (pin "3-RST") (pinfunction "RST_3-RST") (pintype "bidirectional"))
      (node (ref "R1") (pin "2") (pinfunction "2_2") (pintype "passive"))
      (node (ref "R2") (pin "1") (pinfunction "1_1") (pintype "passive"))
    )
    (net (code "42") (name "SWCLK") (class "Default")
      (node (ref "IC1") (pin "45") (pinfunction "(SWCLK/S1:2/T1:0)PA30_45") (pintype "bidirectional"))
      (node (ref "J2") (pin "SWCLK") (pinfunction "SWCLK_SWCLK") (pintype "bidirectional"))
      (node (ref "J3") (pin "4-SWDCLK") (pinfunction "SWCLK_4-SWDCLK") (pintype "bidirectional"))
      (node (ref "R6") (pin "2") (pinfunction "2_2") (pintype "passive"))
    )
    (net (code "43") (name "SWDIO") (class "Default")
      (node (ref "IC1") (pin "46") (pinfunction "(SWDIO/S1:3/T1:1)PA31_46") (pintype "bidirectional"))
      (node (ref "J2") (pin "SWDIO") (pinfunction "SWDIO_SWDIO") (pintype "bidirectional"))
      (node (ref "J3") (pin "5-SWDIO") (pinfunction "SWDIO_5-SWDIO") (pintype "bidirectional"))
    )
    (net (code "44") (name "USB_N") (class "Default")
      (node (ref "D1") (pin "1") (pinfunction "C1_1") (pintype "passive"))
      (node (ref "IC1") (pin "33") (pinfunction "(USBM/S3:2|5:2/T5:0|1:2)PA24_33") (pintype "bidirectional"))
      (node (ref "J1") (pin "A7") (pinfunction "D-_A7") (pintype "bidirectional"))
      (node (ref "J1") (pin "B7") (pinfunction "D-_B7") (pintype "bidirectional"))
    )
    (net (code "45") (name "USB_P") (class "Default")
      (node (ref "D1") (pin "2") (pinfunction "C2_2") (pintype "passive"))
      (node (ref "IC1") (pin "34") (pinfunction "(USBP/S3:3|5:3/T5:1|1:3)PA25_34") (pintype "bidirectional"))
      (node (ref "J1") (pin "A6") (pinfunction "D+_A6") (pintype "bidirectional"))
      (node (ref "J1") (pin "B6") (pinfunction "D+_B6") (pintype "bidirectional"))
    )
    (net (code "46") (name "unconnected-(IC1-(S0:0{slash}T0:0{slash}REFB{slash}AIN4)PA04-Pad9)") (class "Default")
      (node (ref "IC1") (pin "9") (pinfunction "(S0:0/T0:0/REFB/AIN4)PA04_9") (pintype "bidirectional"))
    )
    (net (code "47") (name "unconnected-(IC1-(S0:2{slash}T1:0{slash}AIN6)PA06-Pad11)") (class "Default")
      (node (ref "IC1") (pin "11") (pinfunction "(S0:2/T1:0/AIN6)PA06_11") (pintype "bidirectional"))
    )
    (net (code "48") (name "unconnected-(IC1-(S0:3{slash}T1:1{slash}AIN7)PA07-Pad12)") (class "Default")
      (node (ref "IC1") (pin "12") (pinfunction "(S0:3/T1:1/AIN7)PA07_12") (pintype "bidirectional"))
    )
    (net (code "49") (name "unconnected-(IC1-(S0:3|2:3{slash}T1:1|0:3{slash}AIN19)PA11-Pad16)") (class "Default")
      (node (ref "IC1") (pin "16") (pinfunction "(S0:3|2:3/T1:1|0:3/AIN19)PA11_16") (pintype "bidirectional"))
    )
    (net (code "50") (name "unconnected-(IC1-(S4:0{slash}T4:0{slash}AIN2)PB08-Pad7)") (class "Default")
      (node (ref "IC1") (pin "7") (pinfunction "(S4:0/T4:0/AIN2)PB08_7") (pintype "bidirectional"))
    )
    (net (code "51") (name "unconnected-(IC1-(S4:1{slash}T4:1{slash}AIN3)PB09-Pad8)") (class "Default")
      (node (ref "IC1") (pin "8") (pinfunction "(S4:1/T4:1/AIN3)PB09_8") (pintype "bidirectional"))
    )
    (net (code "52") (name "unconnected-(IC1-(S5:0{slash}T6:0{slash}AIN10)PB02-Pad47)") (class "Default")
      (node (ref "IC1") (pin "47") (pinfunction "(S5:0/T6:0/AIN10)PB02_47") (pintype "bidirectional"))
    )
    (net (code "53") (name "unconnected-(IC1-(S5:3|3:3{slash}T7:1|0:7)PA21-Pad30)") (class "Default")
      (node (ref "IC1") (pin "30") (pinfunction "(S5:3|3:3/T7:1|0:7)PA21_30") (pintype "bidirectional"))
    )
    (net (code "54") (name "unconnected-(IC1-(SCL{slash}S3:1|5:1{slash}T4:1|0:5)PA23-Pad32)") (class "Default")
      (node (ref "IC1") (pin "32") (pinfunction "(SCL/S3:1|5:1/T4:1|0:5)PA23_32") (pintype "bidirectional"))
    )
    (net (code "55") (name "unconnected-(IC1-(XIN32{slash}S1:0{slash}T2:0)PA00-Pad1)") (class "Default")
      (node (ref "IC1") (pin "1") (pinfunction "(XIN32/S1:0/T2:0)PA00_1") (pintype "bidirectional"))
    )
    (net (code "56") (name "unconnected-(IC1-(XIN{slash}S2:2|4:2{slash}T3:0|0:4)PA14-Pad23)") (class "Default")
      (node (ref "IC1") (pin "23") (pinfunction "(XIN/S2:2|4:2/T3:0|0:4)PA14_23") (pintype "bidirectional"))
    )
    (net (code "57") (name "unconnected-(IC1-(XOUT32{slash}S1:1{slash}T2:1)PA01-Pad2)") (class "Default")
      (node (ref "IC1") (pin "2") (pinfunction "(XOUT32/S1:1/T2:1)PA01_2") (pintype "bidirectional"))
    )
    (net (code "58") (name "unconnected-(IC1-(XOUT{slash}S2:3|4:3{slash}T3:1|0:5)PA15-Pad24)") (class "Default")
      (node (ref "IC1") (pin "24") (pinfunction "(XOUT/S2:3|4:3/T3:1|0:5)PA15_24") (pintype "bidirectional"))
    )
    (net (code "59") (name "unconnected-(IC1-PA28-Pad41)") (class "Default")
      (node (ref "IC1") (pin "41") (pinfunction "PA28_41") (pintype "bidirectional"))
    )
    (net (code "60") (name "unconnected-(IC3-PWM-Pad6)") (class "Default")
      (node (ref "IC3") (pin "6") (pinfunction "PWM_6") (pintype "output"))
    )
    (net (code "61") (name "unconnected-(IC3-RDY-Pad5)") (class "Default")
      (node (ref "IC3") (pin "5") (pinfunction "RDY_5") (pintype "output"))
    )
    (net (code "62") (name "unconnected-(IC3-SEL-Pad7)") (class "Default")
      (node (ref "IC3") (pin "7") (pinfunction "SEL_7") (pintype "bidirectional"))
    )
    (net (code "63") (name "unconnected-(IC5-15{slash}IO4-Pad26)") (class "Default")
      (node (ref "IC5") (pin "26") (pinfunction "15/IO4_26") (pintype "bidirectional"))
    )
    (net (code "64") (name "unconnected-(IC5-16{slash}IO5-Pad27)") (class "Default")
      (node (ref "IC5") (pin "27") (pinfunction "16/IO5_27") (pintype "bidirectional"))
    )
    (net (code "65") (name "unconnected-(IC5-18{slash}IO6-Pad1)") (class "Default")
      (node (ref "IC5") (pin "1") (pinfunction "18/IO6_1") (pintype "bidirectional"))
    )
    (net (code "66") (name "unconnected-(IC5-IO3-Pad25)") (class "Default")
      (node (ref "IC5") (pin "25") (pinfunction "IO3_25") (pintype "bidirectional"))
    )
    (net (code "67") (name "unconnected-(IC5-RTC{slash}IO1-Pad21)") (class "Default")
      (node (ref "IC5") (pin "21") (pinfunction "RTC/IO1_21") (pintype "bidirectional"))
    )
    (net (code "68") (name "unconnected-(IC5-SCL-Pad2)") (class "Default")
      (node (ref "IC5") (pin "2") (pinfunction "SCL_2") (pintype "bidirectional"))
    )
    (net (code "69") (name "unconnected-(IC5-SDA-Pad3)") (class "Default")
      (node (ref "IC5") (pin "3") (pinfunction "SDA_3") (pintype "bidirectional"))
    )
    (net (code "70") (name "unconnected-(IC5-TP_1P3V-Pad24)") (class "Default")
      (node (ref "IC5") (pin "24") (pinfunction "TP_1P3V_24") (pintype "bidirectional"))
    )
    (net (code "71") (name "unconnected-(J5-Pad4)") (class "Default")
      (node (ref "J5") (pin "4") (pinfunction "4_4") (pintype "passive"))
    )
  )
)
